# P3.net
KiCad netlist of a schematic drawn in Altium Designer
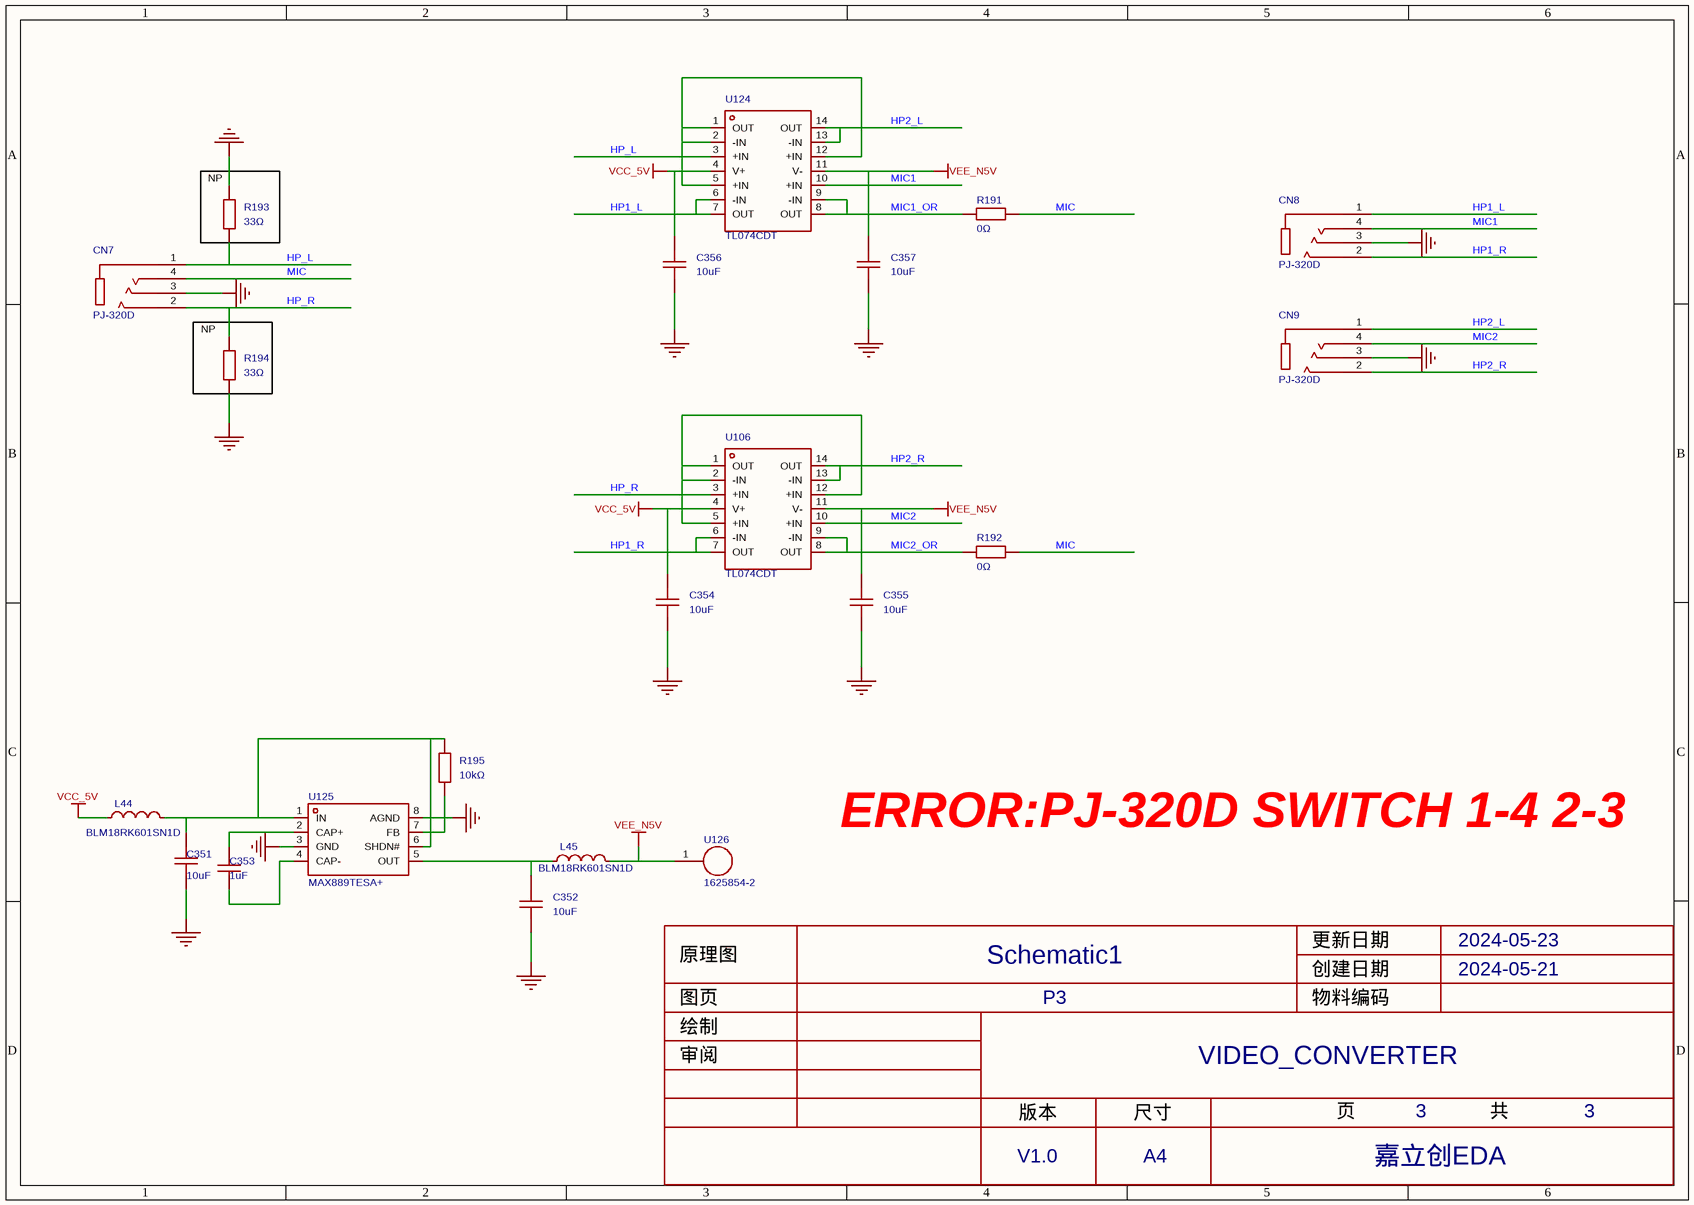
[diagram p0: P3.schdoc]

(export (version "E")
  (design (tool "Eeschema 10.0.6"))
  (components
    (comp (ref "C351")
      (value "10uF")
      (footprint "C0805")
      (description "容值:10uF;精度:±10%;额定电压:50V;材质(温度系数):X5R;")
      (fields
        (field (name "MANUFACTURER") "muRata(村田)")
        (field (name "MANUFACTURER PART") "GRM21BR61H106KE43L")
      )
      (libsource (lib "altium-import") (part "root_1_GRM21BR61H106KE43L_"))
    )
    (comp (ref "C352")
      (value "10uF")
      (footprint "C0805")
      (description "容值:10uF;精度:±10%;额定电压:50V;材质(温度系数):X5R;")
      (fields
        (field (name "MANUFACTURER") "muRata(村田)")
        (field (name "MANUFACTURER PART") "GRM21BR61H106KE43L")
      )
      (libsource (lib "altium-import") (part "root_1_GRM21BR61H106KE43L_"))
    )
    (comp (ref "C353")
      (value "1uF")
      (footprint "C0805")
      (description "容值:1uF;精度:±10%;额定电压:50V;材质(温度系数):X7R;")
      (fields
        (field (name "MANUFACTURER") "muRata(村田)")
        (field (name "MANUFACTURERPART") "GCM21BR71H105KA03L")
      )
      (libsource (lib "altium-import") (part "root_1_GCM21BR71H105KA03L_"))
    )
    (comp (ref "C354")
      (value "10uF")
      (footprint "C0805")
      (description "容值:10uF;精度:±10%;额定电压:50V;材质(温度系数):X5R;")
      (fields
        (field (name "MANUFACTURER") "muRata(村田)")
        (field (name "MANUFACTURER PART") "GRM21BR61H106KE43L")
      )
      (libsource (lib "altium-import") (part "root_1_GRM21BR61H106KE43L_"))
    )
    (comp (ref "C355")
      (value "10uF")
      (footprint "C0805")
      (description "容值:10uF;精度:±10%;额定电压:50V;材质(温度系数):X5R;")
      (fields
        (field (name "MANUFACTURER") "muRata(村田)")
        (field (name "MANUFACTURER PART") "GRM21BR61H106KE43L")
      )
      (libsource (lib "altium-import") (part "root_1_GRM21BR61H106KE43L_"))
    )
    (comp (ref "C356")
      (value "10uF")
      (footprint "C0805")
      (description "容值:10uF;精度:±10%;额定电压:50V;材质(温度系数):X5R;")
      (fields
        (field (name "MANUFACTURER") "muRata(村田)")
        (field (name "MANUFACTURER PART") "GRM21BR61H106KE43L")
      )
      (libsource (lib "altium-import") (part "root_1_GRM21BR61H106KE43L_"))
    )
    (comp (ref "C357")
      (value "10uF")
      (footprint "C0805")
      (description "容值:10uF;精度:±10%;额定电压:50V;材质(温度系数):X5R;")
      (fields
        (field (name "MANUFACTURER") "muRata(村田)")
        (field (name "MANUFACTURER PART") "GRM21BR61H106KE43L")
      )
      (libsource (lib "altium-import") (part "root_1_GRM21BR61H106KE43L_"))
    )
    (comp (ref "CN7")
      (value "PJ-320D")
      (footprint "AUDIO-SMD_PJ-320D")
      (description "连接器类型:3.5mm耳机座;额定电流:300mA;额定电压:50V;工作温度范围:-16℃~+65℃;")
      (fields (field (name "MANUFACTURER") "SHOU HAN(首韩)"))
      (libsource (lib "altium-import") (part "root_0_PJ-320D_C431535_"))
    )
    (comp (ref "CN8")
      (value "PJ-320D")
      (footprint "AUDIO-SMD_PJ-320D")
      (description "连接器类型:3.5mm耳机座;额定电流:300mA;额定电压:50V;工作温度范围:-16℃~+65℃;")
      (fields (field (name "MANUFACTURER") "SHOU HAN(首韩)"))
      (libsource (lib "altium-import") (part "root_0_PJ-320D_C431535_"))
    )
    (comp (ref "CN9")
      (value "PJ-320D")
      (footprint "AUDIO-SMD_PJ-320D")
      (description "连接器类型:3.5mm耳机座;额定电流:300mA;额定电压:50V;工作温度范围:-16℃~+65℃;")
      (fields (field (name "MANUFACTURER") "SHOU HAN(首韩)"))
      (libsource (lib "altium-import") (part "root_0_PJ-320D_C431535_"))
    )
    (comp (ref "L44")
      (value "BLM18RK601SN1D")
      (footprint "L0603")
      (description "标称阻抗@测试频率:600Ω@100MHz;误差:±25%;直流电阻(RDC):600mΩ;")
      (fields (field (name "MANUFACTURER") "muRata(村田)") (field (name "TOLERANCE") "±25%"))
      (libsource (lib "altium-import") (part "root_0_BLM18RK601SN1D_"))
    )
    (comp (ref "L45")
      (value "BLM18RK601SN1D")
      (footprint "L0603")
      (description "标称阻抗@测试频率:600Ω@100MHz;误差:±25%;直流电阻(RDC):600mΩ;")
      (fields (field (name "MANUFACTURER") "muRata(村田)") (field (name "TOLERANCE") "±25%"))
      (libsource (lib "altium-import") (part "root_0_BLM18RK601SN1D_"))
    )
    (comp (ref "R191")
      (value "0Ω")
      (footprint "R0402")
      (description "电阻类型:厚膜电阻;阻值:0Ω;精度:±1%;功率:62.5mW;最大工作电压:50V;温度系数:-;")
      (fields (field (name "MANUFACTURER") "YAGEO(国巨)") (field (name "MANUFACTURERPART") "RC0402FR-070RL"))
      (libsource (lib "altium-import") (part "root_0_RC0402FR-070RL_"))
    )
    (comp (ref "R192")
      (value "0Ω")
      (footprint "R0402")
      (description "电阻类型:厚膜电阻;阻值:0Ω;精度:±1%;功率:62.5mW;最大工作电压:50V;温度系数:-;")
      (fields (field (name "MANUFACTURER") "YAGEO(国巨)") (field (name "MANUFACTURERPART") "RC0402FR-070RL"))
      (libsource (lib "altium-import") (part "root_0_RC0402FR-070RL_"))
    )
    (comp (ref "R193")
      (value "33Ω")
      (footprint "R1206")
      (description "电阻类型:厚膜电阻;阻值:33Ω;精度:±1%;功率:250mW;最大工作电压:200V;温度系数:±200ppm/℃;")
      (fields
        (field (name "MANUFACTURER") "UNI-ROYAL(厚声)")
        (field (name "MANUFACTURER PART") "1206W4F330JT5E")
      )
      (libsource (lib "altium-import") (part "root_1_1206W4F330JT5E_"))
    )
    (comp (ref "R194")
      (value "33Ω")
      (footprint "R1206")
      (description "电阻类型:厚膜电阻;阻值:33Ω;精度:±1%;功率:250mW;最大工作电压:200V;温度系数:±200ppm/℃;")
      (fields
        (field (name "MANUFACTURER") "UNI-ROYAL(厚声)")
        (field (name "MANUFACTURER PART") "1206W4F330JT5E")
      )
      (libsource (lib "altium-import") (part "root_1_1206W4F330JT5E_"))
    )
    (comp (ref "R195")
      (value "10kΩ")
      (footprint "R0402")
      (description "电阻类型:厚膜电阻;阻值:10kΩ;精度:±1%;功率:62.5mW;最大工作电压:50V;温度系数:±100ppm/℃;")
      (fields (field (name "MANUFACTURER") "YAGEO(国巨)") (field (name "MANUFACTURERPART") "RC0402FR-0710KL"))
      (libsource (lib "altium-import") (part "root_3_RC0402FR-0710KL_"))
    )
    (comp (ref "U106")
      (value "TL074CDT")
      (footprint "SOIC-14_L8.7-W3.9-P1.27-LS6.0-BL")
      (description "增益带宽积(GBP):3MHz;输入偏置电流(Ib):30pA;输入失调电压(Vos):3mV;压摆率(SR):13V/us;")
      (fields (field (name "MANUFACTURER") "ST(意法半导体)"))
      (libsource (lib "altium-import") (part "root_0_TL074CDT_"))
    )
    (comp (ref "U124")
      (value "TL074CDT")
      (footprint "SOIC-14_L8.7-W3.9-P1.27-LS6.0-BL")
      (description "增益带宽积(GBP):3MHz;输入偏置电流(Ib):30pA;输入失调电压(Vos):3mV;压摆率(SR):13V/us;")
      (fields (field (name "MANUFACTURER") "ST(意法半导体)"))
      (libsource (lib "altium-import") (part "root_0_TL074CDT_"))
    )
    (comp (ref "U125")
      (value "MAX889TESA+")
      (footprint "SOIC-8_L4.9-W3.9-P1.27-LS6.0-BL")
      (description "功能类型:降压型;输出类型:可调;输入电压:2.7V~5.5V;输出电压:-5.5V~-2.5V;输出电流(最大值):200mA;")
      (fields (field (name "MANUFACTURER") "ADI(亚德诺)/MAXIM(美信)"))
      (libsource (lib "altium-import") (part "root_0_MAX889TESA+_"))
    )
    (comp (ref "U126")
      (value "1625854-2")
      (footprint "TEST-RING")
      (description "PC 测试点 表面贴装")
      (fields (field (name "MANUFACTURER") "TE Connectivity(泰科电子)"))
      (libsource (lib "altium-import") (part "root_3_1625854-2_"))
    )
  )
  (nets
    (net (code "1") (name "/HP1_L") (class "Default")
      (node (ref "CN8") (pin "1") (pinfunction "1_1") (pintype "passive"))
      (node (ref "U124") (pin "6") (pinfunction "-IN_6") (pintype "passive"))
      (node (ref "U124") (pin "7") (pinfunction "OUT_7") (pintype "passive"))
    )
    (net (code "2") (name "/HP1_R") (class "Default")
      (node (ref "CN8") (pin "2") (pinfunction "2_2") (pintype "passive"))
      (node (ref "U106") (pin "6") (pinfunction "-IN_6") (pintype "passive"))
      (node (ref "U106") (pin "7") (pinfunction "OUT_7") (pintype "passive"))
    )
    (net (code "3") (name "/HP2_L") (class "Default")
      (node (ref "CN9") (pin "1") (pinfunction "1_1") (pintype "passive"))
      (node (ref "U124") (pin "13") (pinfunction "-IN_13") (pintype "passive"))
      (node (ref "U124") (pin "14") (pinfunction "OUT_14") (pintype "passive"))
    )
    (net (code "4") (name "/HP2_R") (class "Default")
      (node (ref "CN9") (pin "2") (pinfunction "2_2") (pintype "passive"))
      (node (ref "U106") (pin "13") (pinfunction "-IN_13") (pintype "passive"))
      (node (ref "U106") (pin "14") (pinfunction "OUT_14") (pintype "passive"))
    )
    (net (code "5") (name "/HP_L") (class "Default")
      (node (ref "CN7") (pin "1") (pinfunction "1_1") (pintype "passive"))
      (node (ref "R193") (pin "1") (pinfunction "1_1") (pintype "passive"))
      (node (ref "U124") (pin "3") (pinfunction "+IN_3") (pintype "passive"))
    )
    (net (code "6") (name "/HP_R") (class "Default")
      (node (ref "CN7") (pin "2") (pinfunction "2_2") (pintype "passive"))
      (node (ref "R194") (pin "2") (pinfunction "2_2") (pintype "passive"))
      (node (ref "U106") (pin "3") (pinfunction "+IN_3") (pintype "passive"))
    )
    (net (code "7") (name "/MIC") (class "Default")
      (node (ref "CN7") (pin "4") (pinfunction "4_4") (pintype "passive"))
      (node (ref "R191") (pin "2") (pinfunction "2_2") (pintype "passive"))
      (node (ref "R192") (pin "2") (pinfunction "2_2") (pintype "passive"))
    )
    (net (code "8") (name "/MIC1") (class "Default")
      (node (ref "CN8") (pin "4") (pinfunction "4_4") (pintype "passive"))
      (node (ref "U124") (pin "10") (pinfunction "+IN_10") (pintype "passive"))
    )
    (net (code "9") (name "/MIC1_OR") (class "Default")
      (node (ref "R191") (pin "1") (pinfunction "1_1") (pintype "passive"))
      (node (ref "U124") (pin "8") (pinfunction "OUT_8") (pintype "passive"))
      (node (ref "U124") (pin "9") (pinfunction "-IN_9") (pintype "passive"))
    )
    (net (code "10") (name "/MIC2") (class "Default")
      (node (ref "CN9") (pin "4") (pinfunction "4_4") (pintype "passive"))
      (node (ref "U106") (pin "10") (pinfunction "+IN_10") (pintype "passive"))
    )
    (net (code "11") (name "/MIC2_OR") (class "Default")
      (node (ref "R192") (pin "1") (pinfunction "1_1") (pintype "passive"))
      (node (ref "U106") (pin "8") (pinfunction "OUT_8") (pintype "passive"))
      (node (ref "U106") (pin "9") (pinfunction "-IN_9") (pintype "passive"))
    )
    (net (code "12") (name "GND") (class "Default")
      (node (ref "C351") (pin "1") (pinfunction "1_1") (pintype "passive"))
      (node (ref "C352") (pin "1") (pinfunction "1_1") (pintype "passive"))
      (node (ref "C354") (pin "1") (pinfunction "1_1") (pintype "passive"))
      (node (ref "C355") (pin "1") (pinfunction "1_1") (pintype "passive"))
      (node (ref "C356") (pin "1") (pinfunction "1_1") (pintype "passive"))
      (node (ref "C357") (pin "1") (pinfunction "1_1") (pintype "passive"))
      (node (ref "CN7") (pin "3") (pinfunction "3_3") (pintype "passive"))
      (node (ref "CN8") (pin "3") (pinfunction "3_3") (pintype "passive"))
      (node (ref "CN9") (pin "3") (pinfunction "3_3") (pintype "passive"))
      (node (ref "R193") (pin "2") (pinfunction "2_2") (pintype "passive"))
      (node (ref "R194") (pin "1") (pinfunction "1_1") (pintype "passive"))
      (node (ref "U125") (pin "3") (pinfunction "GND_3") (pintype "passive"))
      (node (ref "U125") (pin "8") (pinfunction "AGND_8") (pintype "passive"))
    )
    (net (code "13") (name "Net-(U106-+IN-Pad12)") (class "Default")
      (node (ref "U106") (pin "1") (pinfunction "OUT_1") (pintype "passive"))
      (node (ref "U106") (pin "12") (pinfunction "+IN_12") (pintype "passive"))
      (node (ref "U106") (pin "2") (pinfunction "-IN_2") (pintype "passive"))
      (node (ref "U106") (pin "5") (pinfunction "+IN_5") (pintype "passive"))
    )
    (net (code "14") (name "Net-(U124-+IN-Pad12)") (class "Default")
      (node (ref "U124") (pin "1") (pinfunction "OUT_1") (pintype "passive"))
      (node (ref "U124") (pin "12") (pinfunction "+IN_12") (pintype "passive"))
      (node (ref "U124") (pin "2") (pinfunction "-IN_2") (pintype "passive"))
      (node (ref "U124") (pin "5") (pinfunction "+IN_5") (pintype "passive"))
    )
    (net (code "15") (name "Net-(U125-CAP+)") (class "Default")
      (node (ref "C353") (pin "2") (pinfunction "2_2") (pintype "passive"))
      (node (ref "U125") (pin "2") (pinfunction "CAP+_2") (pintype "passive"))
    )
    (net (code "16") (name "Net-(U125-CAP-)") (class "Default")
      (node (ref "C353") (pin "1") (pinfunction "1_1") (pintype "passive"))
      (node (ref "U125") (pin "4") (pinfunction "CAP-_4") (pintype "passive"))
    )
    (net (code "17") (name "Net-(U125-FB)") (class "Default")
      (node (ref "R195") (pin "2") (pinfunction "2_2") (pintype "passive"))
      (node (ref "U125") (pin "7") (pinfunction "FB_7") (pintype "passive"))
    )
    (net (code "18") (name "Net-(U125-IN)") (class "Default")
      (node (ref "C351") (pin "2") (pinfunction "2_2") (pintype "passive"))
      (node (ref "L44") (pin "2") (pinfunction "2_2") (pintype "passive"))
      (node (ref "R195") (pin "1") (pinfunction "1_1") (pintype "passive"))
      (node (ref "U125") (pin "1") (pinfunction "IN_1") (pintype "passive"))
      (node (ref "U125") (pin "6") (pinfunction "SHDN#_6") (pintype "passive"))
    )
    (net (code "19") (name "Net-(U125-OUT)") (class "Default")
      (node (ref "C352") (pin "2") (pinfunction "2_2") (pintype "passive"))
      (node (ref "L45") (pin "1") (pinfunction "1_1") (pintype "passive"))
      (node (ref "U125") (pin "5") (pinfunction "OUT_5") (pintype "passive"))
    )
    (net (code "20") (name "VCC_5V") (class "Default")
      (node (ref "C354") (pin "2") (pinfunction "2_2") (pintype "passive"))
      (node (ref "C356") (pin "2") (pinfunction "2_2") (pintype "passive"))
      (node (ref "L44") (pin "1") (pinfunction "1_1") (pintype "passive"))
      (node (ref "U106") (pin "4") (pinfunction "V+_4") (pintype "passive"))
      (node (ref "U124") (pin "4") (pinfunction "V+_4") (pintype "passive"))
    )
    (net (code "21") (name "VEE_N5V") (class "Default")
      (node (ref "C355") (pin "2") (pinfunction "2_2") (pintype "passive"))
      (node (ref "C357") (pin "2") (pinfunction "2_2") (pintype "passive"))
      (node (ref "L45") (pin "2") (pinfunction "2_2") (pintype "passive"))
      (node (ref "U106") (pin "11") (pinfunction "V-_11") (pintype "passive"))
      (node (ref "U124") (pin "11") (pinfunction "V-_11") (pintype "passive"))
      (node (ref "U126") (pin "1") (pinfunction "1_1") (pintype "passive"))
    )
  )
)
